# icestamp1k.net
KiCad netlist of a schematic drawn in EAGLE
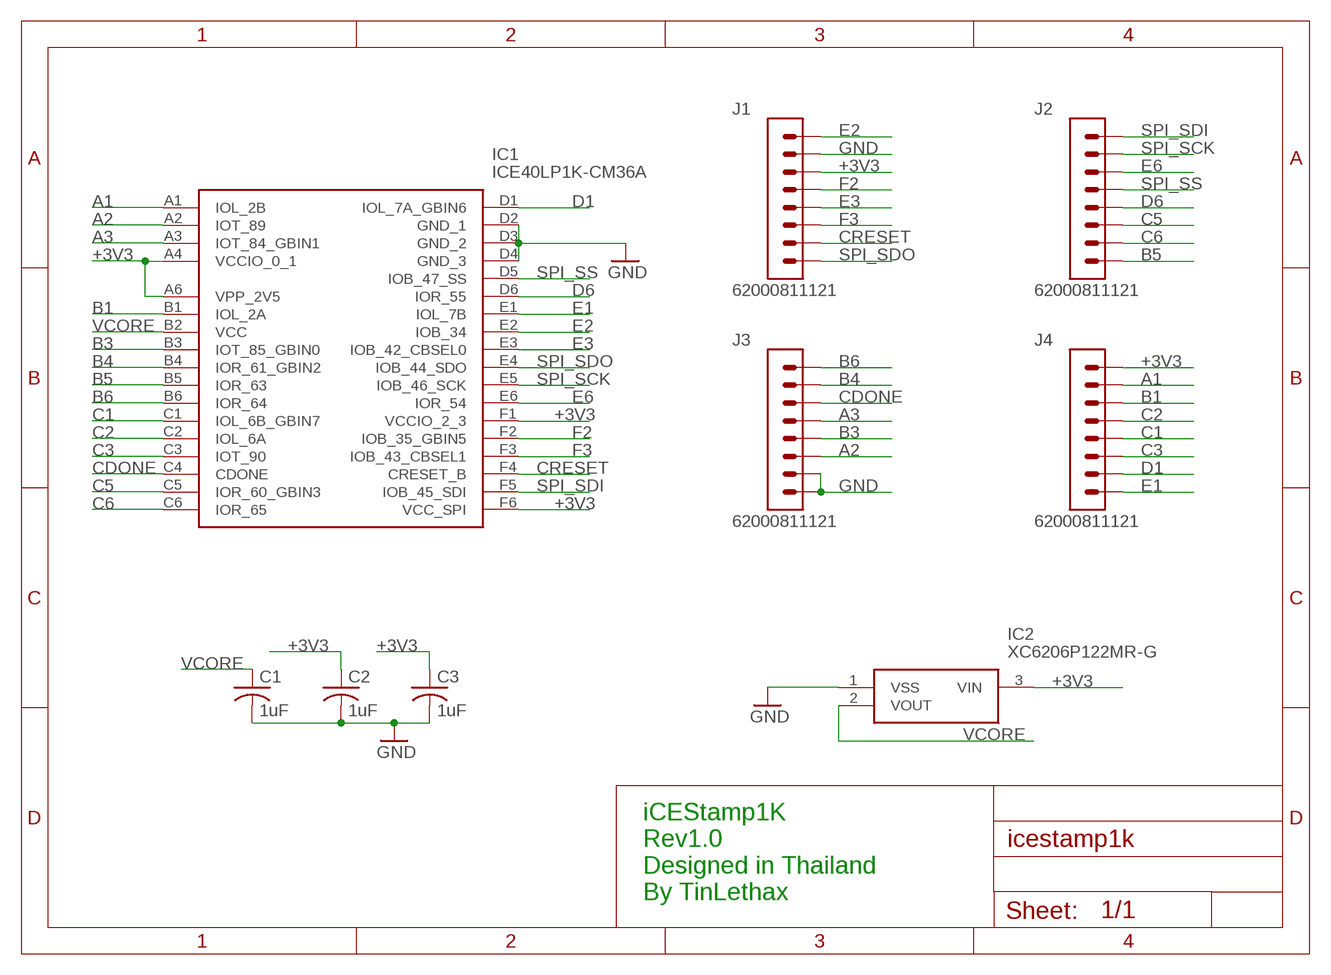
[diagram p0: schematic, sheet 1]

(export (version "E")
  (design (tool "Eeschema 10.0.6"))
  (components
    (comp (ref "C1")
      (value "1uF")
      (footprint "eagle-import:C0603")
      (libsource (lib "eagle-import") (part "C-USC0603"))
    )
    (comp (ref "C2")
      (value "1uF")
      (footprint "eagle-import:C0603")
      (libsource (lib "eagle-import") (part "C-USC0603"))
    )
    (comp (ref "C3")
      (value "1uF")
      (footprint "eagle-import:C0603")
      (libsource (lib "eagle-import") (part "C-USC0603"))
    )
    (comp (ref "IC1")
      (value "ICE40LP1K-CM36A")
      (footprint "eagle-import:BGA36C40P6X6_250X250X100")
      (fields (field (name "MOUSER_PART_NUMBER") "842-ICE40LP1K-CM36A"))
      (libsource (lib "eagle-import") (part "ICE40LP1K-CM36A"))
    )
    (comp (ref "IC2")
      (value "XC6206P122MR-G")
      (footprint "eagle-import:SOT95P280X130-3N")
      (fields (field (name "MOUSER_PART_NUMBER") "865-XC6206P122MR-G"))
      (libsource (lib "eagle-import") (part "XC6206P122MR-G"))
    )
    (comp (ref "J1")
      (value "62000811121")
      (footprint "eagle-import:62000811121")
      (fields (field (name "MANUFACTURER") "Würth Elektronik ") (field (name "CREATED_BY") "PCBLayout.com"))
      (libsource (lib "eagle-import") (part "62000811121"))
    )
    (comp (ref "J2")
      (value "62000811121")
      (footprint "eagle-import:62000811121")
      (fields (field (name "MANUFACTURER") "Würth Elektronik ") (field (name "CREATED_BY") "PCBLayout.com"))
      (libsource (lib "eagle-import") (part "62000811121"))
    )
    (comp (ref "J3")
      (value "62000811121")
      (footprint "eagle-import:62000811121")
      (fields (field (name "MANUFACTURER") "Würth Elektronik ") (field (name "CREATED_BY") "PCBLayout.com"))
      (libsource (lib "eagle-import") (part "62000811121"))
    )
    (comp (ref "J4")
      (value "62000811121")
      (footprint "eagle-import:62000811121")
      (fields (field (name "MANUFACTURER") "Würth Elektronik ") (field (name "CREATED_BY") "PCBLayout.com"))
      (libsource (lib "eagle-import") (part "62000811121"))
    )
  )
  (nets
    (net (code "1") (name "/+3V3") (class "Default")
      (node (ref "C2") (pin "1") (pinfunction "1_1") (pintype "passive"))
      (node (ref "C3") (pin "1") (pinfunction "1_1") (pintype "passive"))
      (node (ref "IC1") (pin "A4") (pinfunction "VCCIO_0_1_A4") (pintype "bidirectional"))
      (node (ref "IC1") (pin "A6") (pinfunction "VPP_2V5_A6") (pintype "bidirectional"))
      (node (ref "IC1") (pin "F1") (pinfunction "VCCIO_2_3_F1") (pintype "bidirectional"))
      (node (ref "IC1") (pin "F6") (pinfunction "VCC_SPI_F6") (pintype "bidirectional"))
      (node (ref "IC2") (pin "3") (pinfunction "VIN_3") (pintype "bidirectional"))
      (node (ref "J1") (pin "3") (pinfunction "3_3") (pintype "passive"))
      (node (ref "J4") (pin "1") (pinfunction "1_1") (pintype "passive"))
    )
    (net (code "2") (name "/A1") (class "Default")
      (node (ref "IC1") (pin "A1") (pinfunction "IOL_2B_A1") (pintype "bidirectional"))
      (node (ref "J4") (pin "2") (pinfunction "2_2") (pintype "passive"))
    )
    (net (code "3") (name "/A2") (class "Default")
      (node (ref "IC1") (pin "A2") (pinfunction "IOT_89_A2") (pintype "bidirectional"))
      (node (ref "J3") (pin "6") (pinfunction "6_6") (pintype "passive"))
    )
    (net (code "4") (name "/A3") (class "Default")
      (node (ref "IC1") (pin "A3") (pinfunction "IOT_84_GBIN1_A3") (pintype "bidirectional"))
      (node (ref "J3") (pin "4") (pinfunction "4_4") (pintype "passive"))
    )
    (net (code "5") (name "/B1") (class "Default")
      (node (ref "IC1") (pin "B1") (pinfunction "IOL_2A_B1") (pintype "bidirectional"))
      (node (ref "J4") (pin "3") (pinfunction "3_3") (pintype "passive"))
    )
    (net (code "6") (name "/B3") (class "Default")
      (node (ref "IC1") (pin "B3") (pinfunction "IOT_85_GBIN0_B3") (pintype "bidirectional"))
      (node (ref "J3") (pin "5") (pinfunction "5_5") (pintype "passive"))
    )
    (net (code "7") (name "/B4") (class "Default")
      (node (ref "IC1") (pin "B4") (pinfunction "IOR_61_GBIN2_B4") (pintype "bidirectional"))
      (node (ref "J3") (pin "2") (pinfunction "2_2") (pintype "passive"))
    )
    (net (code "8") (name "/B5") (class "Default")
      (node (ref "IC1") (pin "B5") (pinfunction "IOR_63_B5") (pintype "bidirectional"))
      (node (ref "J2") (pin "8") (pinfunction "8_8") (pintype "passive"))
    )
    (net (code "9") (name "/B6") (class "Default")
      (node (ref "IC1") (pin "B6") (pinfunction "IOR_64_B6") (pintype "bidirectional"))
      (node (ref "J3") (pin "1") (pinfunction "1_1") (pintype "passive"))
    )
    (net (code "10") (name "/C1") (class "Default")
      (node (ref "IC1") (pin "C1") (pinfunction "IOL_6B_GBIN7_C1") (pintype "bidirectional"))
      (node (ref "J4") (pin "5") (pinfunction "5_5") (pintype "passive"))
    )
    (net (code "11") (name "/C2") (class "Default")
      (node (ref "IC1") (pin "C2") (pinfunction "IOL_6A_C2") (pintype "bidirectional"))
      (node (ref "J4") (pin "4") (pinfunction "4_4") (pintype "passive"))
    )
    (net (code "12") (name "/C3") (class "Default")
      (node (ref "IC1") (pin "C3") (pinfunction "IOT_90_C3") (pintype "bidirectional"))
      (node (ref "J4") (pin "6") (pinfunction "6_6") (pintype "passive"))
    )
    (net (code "13") (name "/C5") (class "Default")
      (node (ref "IC1") (pin "C5") (pinfunction "IOR_60_GBIN3_C5") (pintype "bidirectional"))
      (node (ref "J2") (pin "6") (pinfunction "6_6") (pintype "passive"))
    )
    (net (code "14") (name "/C6") (class "Default")
      (node (ref "IC1") (pin "C6") (pinfunction "IOR_65_C6") (pintype "bidirectional"))
      (node (ref "J2") (pin "7") (pinfunction "7_7") (pintype "passive"))
    )
    (net (code "15") (name "/CDONE") (class "Default")
      (node (ref "IC1") (pin "C4") (pinfunction "CDONE_C4") (pintype "bidirectional"))
      (node (ref "J3") (pin "3") (pinfunction "3_3") (pintype "passive"))
    )
    (net (code "16") (name "/CRESET") (class "Default")
      (node (ref "IC1") (pin "F4") (pinfunction "CRESET_B_F4") (pintype "bidirectional"))
      (node (ref "J1") (pin "7") (pinfunction "7_7") (pintype "passive"))
    )
    (net (code "17") (name "/D1") (class "Default")
      (node (ref "IC1") (pin "D1") (pinfunction "IOL_7A_GBIN6_D1") (pintype "bidirectional"))
      (node (ref "J4") (pin "7") (pinfunction "7_7") (pintype "passive"))
    )
    (net (code "18") (name "/D6") (class "Default")
      (node (ref "IC1") (pin "D6") (pinfunction "IOR_55_D6") (pintype "bidirectional"))
      (node (ref "J2") (pin "5") (pinfunction "5_5") (pintype "passive"))
    )
    (net (code "19") (name "/E1") (class "Default")
      (node (ref "IC1") (pin "E1") (pinfunction "IOL_7B_E1") (pintype "bidirectional"))
      (node (ref "J4") (pin "8") (pinfunction "8_8") (pintype "passive"))
    )
    (net (code "20") (name "/E2") (class "Default")
      (node (ref "IC1") (pin "E2") (pinfunction "IOB_34_E2") (pintype "bidirectional"))
      (node (ref "J1") (pin "1") (pinfunction "1_1") (pintype "passive"))
    )
    (net (code "21") (name "/E3") (class "Default")
      (node (ref "IC1") (pin "E3") (pinfunction "IOB_42_CBSEL0_E3") (pintype "bidirectional"))
      (node (ref "J1") (pin "5") (pinfunction "5_5") (pintype "passive"))
    )
    (net (code "22") (name "/E6") (class "Default")
      (node (ref "IC1") (pin "E6") (pinfunction "IOR_54_E6") (pintype "bidirectional"))
      (node (ref "J2") (pin "3") (pinfunction "3_3") (pintype "passive"))
    )
    (net (code "23") (name "/F2") (class "Default")
      (node (ref "IC1") (pin "F2") (pinfunction "IOB_35_GBIN5_F2") (pintype "bidirectional"))
      (node (ref "J1") (pin "4") (pinfunction "4_4") (pintype "passive"))
    )
    (net (code "24") (name "/F3") (class "Default")
      (node (ref "IC1") (pin "F3") (pinfunction "IOB_43_CBSEL1_F3") (pintype "bidirectional"))
      (node (ref "J1") (pin "6") (pinfunction "6_6") (pintype "passive"))
    )
    (net (code "25") (name "/SPI_SCK") (class "Default")
      (node (ref "IC1") (pin "E5") (pinfunction "IOB_46_SCK_E5") (pintype "bidirectional"))
      (node (ref "J2") (pin "2") (pinfunction "2_2") (pintype "passive"))
    )
    (net (code "26") (name "/SPI_SDI") (class "Default")
      (node (ref "IC1") (pin "F5") (pinfunction "IOB_45_SDI_F5") (pintype "bidirectional"))
      (node (ref "J2") (pin "1") (pinfunction "1_1") (pintype "passive"))
    )
    (net (code "27") (name "/SPI_SDO") (class "Default")
      (node (ref "IC1") (pin "E4") (pinfunction "IOB_44_SDO_E4") (pintype "bidirectional"))
      (node (ref "J1") (pin "8") (pinfunction "8_8") (pintype "passive"))
    )
    (net (code "28") (name "/SPI_SS") (class "Default")
      (node (ref "IC1") (pin "D5") (pinfunction "IOB_47_SS_D5") (pintype "bidirectional"))
      (node (ref "J2") (pin "4") (pinfunction "4_4") (pintype "passive"))
    )
    (net (code "29") (name "/VCORE") (class "Default")
      (node (ref "C1") (pin "1") (pinfunction "1_1") (pintype "passive"))
      (node (ref "IC1") (pin "B2") (pinfunction "VCC_B2") (pintype "bidirectional"))
      (node (ref "IC2") (pin "2") (pinfunction "VOUT_2") (pintype "bidirectional"))
    )
    (net (code "30") (name "GND") (class "Default")
      (node (ref "C1") (pin "2") (pinfunction "2_2") (pintype "passive"))
      (node (ref "C2") (pin "2") (pinfunction "2_2") (pintype "passive"))
      (node (ref "C3") (pin "2") (pinfunction "2_2") (pintype "passive"))
      (node (ref "IC1") (pin "D2") (pinfunction "GND_1_D2") (pintype "bidirectional"))
      (node (ref "IC1") (pin "D3") (pinfunction "GND_2_D3") (pintype "bidirectional"))
      (node (ref "IC1") (pin "D4") (pinfunction "GND_3_D4") (pintype "bidirectional"))
      (node (ref "IC2") (pin "1") (pinfunction "VSS_1") (pintype "bidirectional"))
      (node (ref "J1") (pin "2") (pinfunction "2_2") (pintype "passive"))
      (node (ref "J3") (pin "7") (pinfunction "7_7") (pintype "passive"))
      (node (ref "J3") (pin "8") (pinfunction "8_8") (pintype "passive"))
    )
  )
)
